# IO.net
KiCad netlist of a schematic drawn in Altium Designer
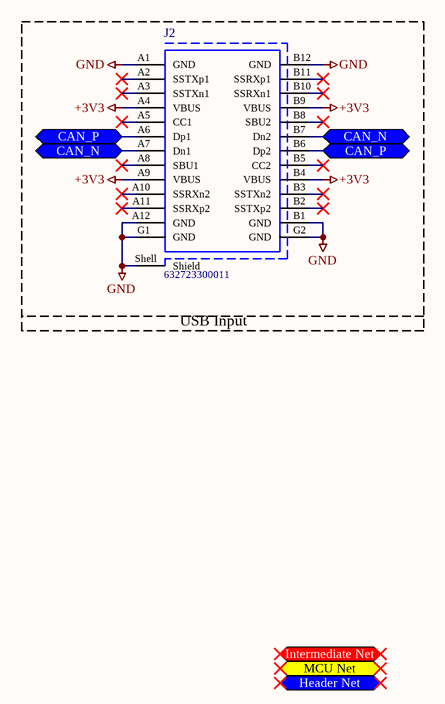
[diagram p0: IO.SchDoc]

(export (version "E")
  (design (tool "Eeschema 10.0.6"))
  (components
    (comp (ref "J2")
      (value "632723300011")
      (footprint "632723300011")
      (description "USB 3.1 Type C Receptacle WR-COM, Horizontal, SMT / THT")
      (fields (field (name "MANUFACTURER") "Wurth Elektronik") (field (name "PUBLISHER") "WurthElektronik"))
      (libsource (lib "Altium Content Vault") (part "WE-632723X00011"))
    )
  )
  (nets
    (net (code "1") (name "+3V3") (class "Default")
      (node (ref "J2") (pin "A4") (pinfunction "VBUS_A4") (pintype "passive"))
      (node (ref "J2") (pin "A9") (pinfunction "VBUS_A9") (pintype "passive"))
      (node (ref "J2") (pin "B4") (pinfunction "VBUS_B4") (pintype "passive"))
      (node (ref "J2") (pin "B9") (pinfunction "VBUS_B9") (pintype "passive"))
    )
    (net (code "2") (name "/CAN_N") (class "Default")
      (node (ref "J2") (pin "A7") (pinfunction "Dn1_A7") (pintype "passive"))
      (node (ref "J2") (pin "B7") (pinfunction "Dn2_B7") (pintype "passive"))
    )
    (net (code "3") (name "/CAN_P") (class "Default")
      (node (ref "J2") (pin "A6") (pinfunction "Dp1_A6") (pintype "passive"))
      (node (ref "J2") (pin "B6") (pinfunction "Dp2_B6") (pintype "passive"))
    )
    (net (code "7") (name "GND") (class "Default")
      (node (ref "J2") (pin "A1") (pinfunction "GND_A1") (pintype "passive"))
      (node (ref "J2") (pin "A12") (pinfunction "GND_A12") (pintype "passive"))
      (node (ref "J2") (pin "B1") (pinfunction "GND_B1") (pintype "passive"))
      (node (ref "J2") (pin "B12") (pinfunction "GND_B12") (pintype "passive"))
      (node (ref "J2") (pin "G1") (pinfunction "GND_G1") (pintype "passive"))
      (node (ref "J2") (pin "G2") (pinfunction "GND_G2") (pintype "passive"))
      (node (ref "J2") (pin "Shell") (pinfunction "Shield_Shell") (pintype "passive"))
    )
    (net (code "8") (name "unconnected-(J2-CC1-PadA5)") (class "Default")
      (node (ref "J2") (pin "A5") (pinfunction "CC1_A5") (pintype "passive+no_connect"))
    )
    (net (code "9") (name "unconnected-(J2-CC2-PadB5)") (class "Default")
      (node (ref "J2") (pin "B5") (pinfunction "CC2_B5") (pintype "passive+no_connect"))
    )
    (net (code "10") (name "unconnected-(J2-SBU1-PadA8)") (class "Default")
      (node (ref "J2") (pin "A8") (pinfunction "SBU1_A8") (pintype "passive+no_connect"))
    )
    (net (code "11") (name "unconnected-(J2-SBU2-PadB8)") (class "Default")
      (node (ref "J2") (pin "B8") (pinfunction "SBU2_B8") (pintype "passive+no_connect"))
    )
    (net (code "12") (name "unconnected-(J2-SSRXn1-PadB10)") (class "Default")
      (node (ref "J2") (pin "B10") (pinfunction "SSRXn1_B10") (pintype "passive+no_connect"))
    )
    (net (code "13") (name "unconnected-(J2-SSRXn2-PadA10)") (class "Default")
      (node (ref "J2") (pin "A10") (pinfunction "SSRXn2_A10") (pintype "passive+no_connect"))
    )
    (net (code "14") (name "unconnected-(J2-SSRXp1-PadB11)") (class "Default")
      (node (ref "J2") (pin "B11") (pinfunction "SSRXp1_B11") (pintype "passive+no_connect"))
    )
    (net (code "15") (name "unconnected-(J2-SSRXp2-PadA11)") (class "Default")
      (node (ref "J2") (pin "A11") (pinfunction "SSRXp2_A11") (pintype "passive+no_connect"))
    )
    (net (code "16") (name "unconnected-(J2-SSTXn1-PadA3)") (class "Default")
      (node (ref "J2") (pin "A3") (pinfunction "SSTXn1_A3") (pintype "passive+no_connect"))
    )
    (net (code "17") (name "unconnected-(J2-SSTXn2-PadB3)") (class "Default")
      (node (ref "J2") (pin "B3") (pinfunction "SSTXn2_B3") (pintype "passive+no_connect"))
    )
    (net (code "18") (name "unconnected-(J2-SSTXp1-PadA2)") (class "Default")
      (node (ref "J2") (pin "A2") (pinfunction "SSTXp1_A2") (pintype "passive+no_connect"))
    )
    (net (code "19") (name "unconnected-(J2-SSTXp2-PadB2)") (class "Default")
      (node (ref "J2") (pin "B2") (pinfunction "SSTXp2_B2") (pintype "passive+no_connect"))
    )
  )
)
